# HB-UNI-SenAct-8-8-RC_V1_2.net
KiCad netlist of a schematic drawn in EAGLE
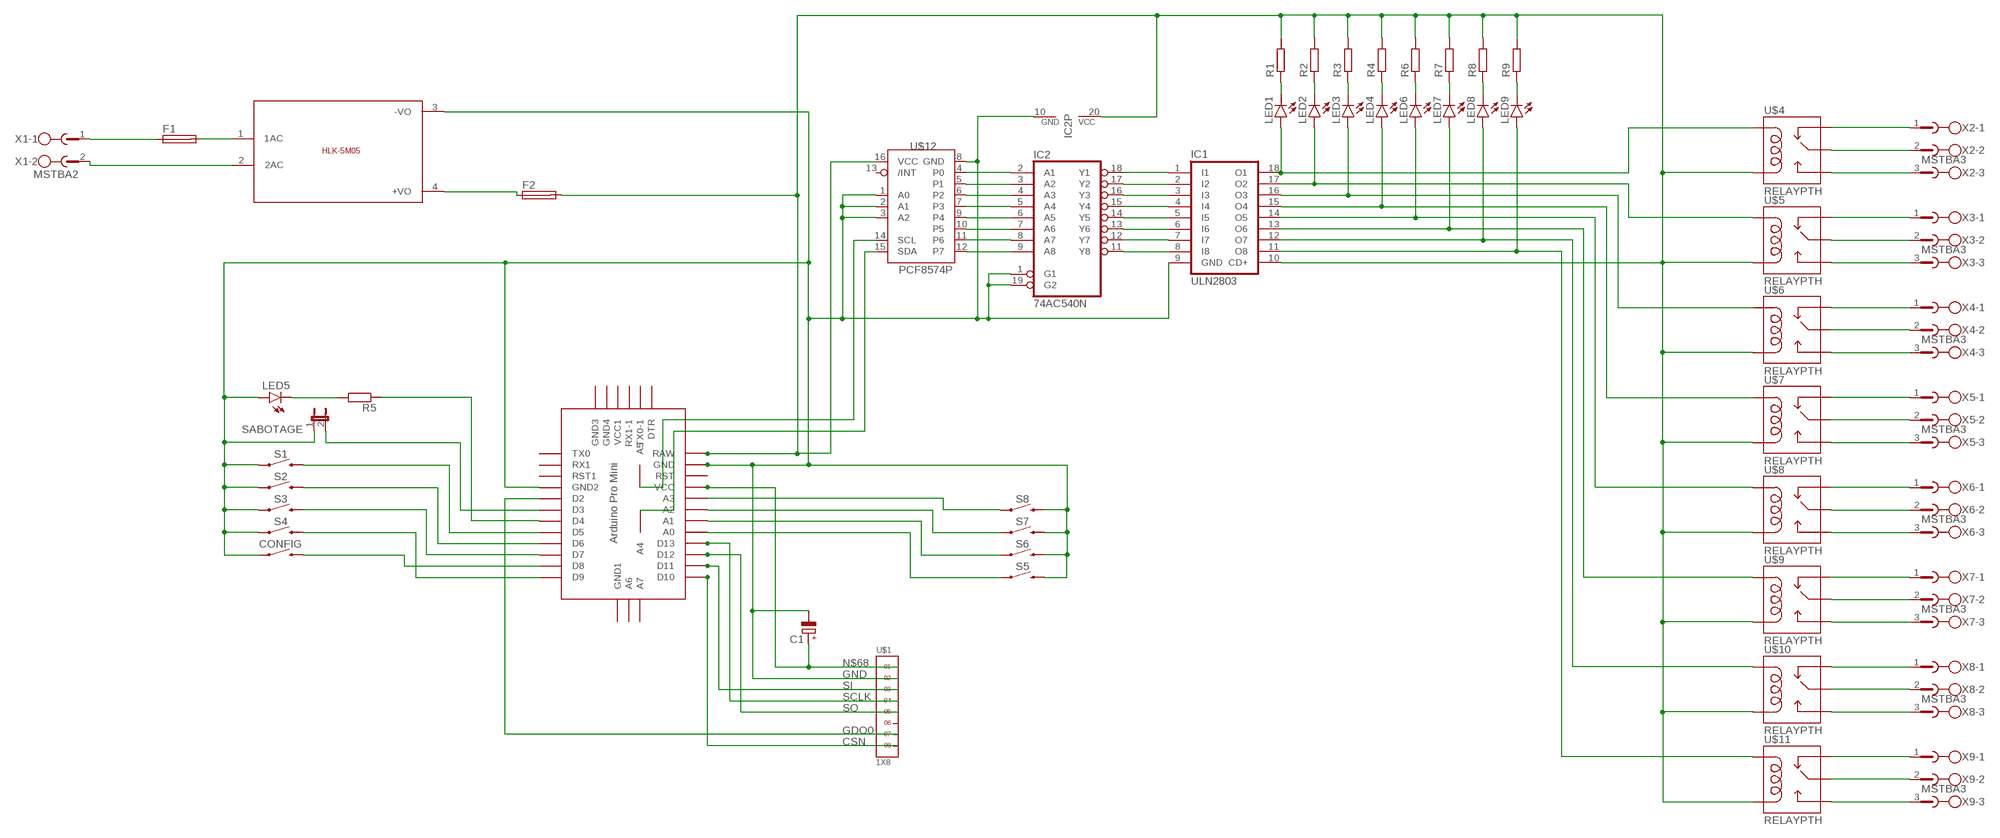
[diagram p0: schematic, sheet 1]

(export (version "E")
  (design (tool "Eeschema 10.0.6"))
  (components
    (comp (ref "C1")
      (value "CPOL-EUE2.5-5")
      (footprint "eagle-import:E2,5-5")
      (libsource (lib "eagle-import") (part "CPOL-EUE2.5-5"))
    )
    (comp (ref "CONFIG")
      (value "MOMENTARY-SWITCH-SPST-PTH-6.0MM-KIT")
      (footprint "eagle-import:TACTILE_SWITCH_PTH_6.0MM_KIT")
      (libsource (lib "eagle-import") (part "MOMENTARY-SWITCH-SPST-PTH-6.0MM-KIT"))
    )
    (comp (ref "F1")
      (value "SH22,5A")
      (footprint "eagle-import:SH22,5A")
      (fields (field (name "MPN") "0031.7701.11"))
      (libsource (lib "eagle-import") (part "SH22,5A"))
    )
    (comp (ref "F2")
      (value "SH22,5A")
      (footprint "eagle-import:SH22,5A")
      (fields (field (name "MPN") "0031.7701.11"))
      (libsource (lib "eagle-import") (part "SH22,5A"))
    )
    (comp (ref "IC1")
      (value "ULN2803")
      (footprint "eagle-import:DIL18")
      (libsource (lib "eagle-import") (part "ULN2803A"))
    )
    (comp (ref "IC2")
      (value "74AC540N")
      (footprint "eagle-import:DIL20")
      (libsource (lib "eagle-import") (part "74540NAC"))
    )
    (comp (ref "LED1")
      (value "LED3MM")
      (footprint "eagle-import:LED3MM")
      (libsource (lib "eagle-import") (part "LED3MM"))
    )
    (comp (ref "LED2")
      (value "LED3MM")
      (footprint "eagle-import:LED3MM")
      (libsource (lib "eagle-import") (part "LED3MM"))
    )
    (comp (ref "LED3")
      (value "LED3MM")
      (footprint "eagle-import:LED3MM")
      (libsource (lib "eagle-import") (part "LED3MM"))
    )
    (comp (ref "LED4")
      (value "LED3MM")
      (footprint "eagle-import:LED3MM")
      (libsource (lib "eagle-import") (part "LED3MM"))
    )
    (comp (ref "LED5")
      (value "LED3MM")
      (footprint "eagle-import:LED3MM")
      (libsource (lib "eagle-import") (part "LED3MM"))
    )
    (comp (ref "LED6")
      (value "LED3MM")
      (footprint "eagle-import:LED3MM")
      (libsource (lib "eagle-import") (part "LED3MM"))
    )
    (comp (ref "LED7")
      (value "LED3MM")
      (footprint "eagle-import:LED3MM")
      (libsource (lib "eagle-import") (part "LED3MM"))
    )
    (comp (ref "LED8")
      (value "LED3MM")
      (footprint "eagle-import:LED3MM")
      (libsource (lib "eagle-import") (part "LED3MM"))
    )
    (comp (ref "LED9")
      (value "LED3MM")
      (footprint "eagle-import:LED3MM")
      (libsource (lib "eagle-import") (part "LED3MM"))
    )
    (comp (ref "R1")
      (value "R-EU_0309/10")
      (footprint "eagle-import:0309_10")
      (libsource (lib "eagle-import") (part "R-EU_0309/10"))
    )
    (comp (ref "R2")
      (value "R-EU_0309/10")
      (footprint "eagle-import:0309_10")
      (libsource (lib "eagle-import") (part "R-EU_0309/10"))
    )
    (comp (ref "R3")
      (value "R-EU_0309/10")
      (footprint "eagle-import:0309_10")
      (libsource (lib "eagle-import") (part "R-EU_0309/10"))
    )
    (comp (ref "R4")
      (value "R-EU_0309/10")
      (footprint "eagle-import:0309_10")
      (libsource (lib "eagle-import") (part "R-EU_0309/10"))
    )
    (comp (ref "R5")
      (value "R-EU_0309/10")
      (footprint "eagle-import:0309_10")
      (libsource (lib "eagle-import") (part "R-EU_0309/10"))
    )
    (comp (ref "R6")
      (value "R-EU_0309/10")
      (footprint "eagle-import:0309_10")
      (libsource (lib "eagle-import") (part "R-EU_0309/10"))
    )
    (comp (ref "R7")
      (value "R-EU_0309/10")
      (footprint "eagle-import:0309_10")
      (libsource (lib "eagle-import") (part "R-EU_0309/10"))
    )
    (comp (ref "R8")
      (value "R-EU_0309/10")
      (footprint "eagle-import:0309_10")
      (libsource (lib "eagle-import") (part "R-EU_0309/10"))
    )
    (comp (ref "R9")
      (value "R-EU_0309/10")
      (footprint "eagle-import:0309_10")
      (libsource (lib "eagle-import") (part "R-EU_0309/10"))
    )
    (comp (ref "S1")
      (value "MOMENTARY-SWITCH-SPST-PTH-6.0MM")
      (footprint "eagle-import:TACTILE_SWITCH_PTH_6.0MM")
      (libsource (lib "eagle-import") (part "MOMENTARY-SWITCH-SPST-PTH-6.0MM"))
    )
    (comp (ref "S2")
      (value "MOMENTARY-SWITCH-SPST-PTH-6.0MM-KIT")
      (footprint "eagle-import:TACTILE_SWITCH_PTH_6.0MM_KIT")
      (libsource (lib "eagle-import") (part "MOMENTARY-SWITCH-SPST-PTH-6.0MM-KIT"))
    )
    (comp (ref "S3")
      (value "MOMENTARY-SWITCH-SPST-PTH-6.0MM-KIT")
      (footprint "eagle-import:TACTILE_SWITCH_PTH_6.0MM_KIT")
      (libsource (lib "eagle-import") (part "MOMENTARY-SWITCH-SPST-PTH-6.0MM-KIT"))
    )
    (comp (ref "S4")
      (value "MOMENTARY-SWITCH-SPST-PTH-6.0MM-KIT")
      (footprint "eagle-import:TACTILE_SWITCH_PTH_6.0MM_KIT")
      (libsource (lib "eagle-import") (part "MOMENTARY-SWITCH-SPST-PTH-6.0MM-KIT"))
    )
    (comp (ref "S5")
      (value "MOMENTARY-SWITCH-SPST-PTH-6.0MM-KIT")
      (footprint "eagle-import:TACTILE_SWITCH_PTH_6.0MM_KIT")
      (libsource (lib "eagle-import") (part "MOMENTARY-SWITCH-SPST-PTH-6.0MM-KIT"))
    )
    (comp (ref "S6")
      (value "MOMENTARY-SWITCH-SPST-PTH-6.0MM-KIT")
      (footprint "eagle-import:TACTILE_SWITCH_PTH_6.0MM_KIT")
      (libsource (lib "eagle-import") (part "MOMENTARY-SWITCH-SPST-PTH-6.0MM-KIT"))
    )
    (comp (ref "S7")
      (value "MOMENTARY-SWITCH-SPST-PTH-6.0MM-KIT")
      (footprint "eagle-import:TACTILE_SWITCH_PTH_6.0MM_KIT")
      (libsource (lib "eagle-import") (part "MOMENTARY-SWITCH-SPST-PTH-6.0MM-KIT"))
    )
    (comp (ref "S8")
      (value "MOMENTARY-SWITCH-SPST-PTH-6.0MM-KIT")
      (footprint "eagle-import:TACTILE_SWITCH_PTH_6.0MM_KIT")
      (libsource (lib "eagle-import") (part "MOMENTARY-SWITCH-SPST-PTH-6.0MM-KIT"))
    )
    (comp (ref "SABOTAGE")
      (value "JP1E")
      (footprint "eagle-import:JP1")
      (libsource (lib "eagle-import") (part "JP1E"))
    )
    (comp (ref "U$1")
      (value "1X8")
      (footprint "eagle-import:1X8")
      (libsource (lib "eagle-import") (part "1X8"))
    )
    (comp (ref "U$2")
      (value "ABK-PRO-MINI")
      (footprint "eagle-import:ABK-PRO-MINI")
      (libsource (lib "eagle-import") (part "ABK-PRO-MINI"))
    )
    (comp (ref "U$3")
      (value "5VDC/5W")
      (footprint "eagle-import:HLK-5M05")
      (libsource (lib "eagle-import") (part "HLK-5M05"))
    )
    (comp (ref "U$4")
      (value "RELAYPTH")
      (footprint "eagle-import:SRD-05VDC-SL-C")
      (libsource (lib "eagle-import") (part "RELAYPTH"))
    )
    (comp (ref "U$5")
      (value "RELAYPTH")
      (footprint "eagle-import:SRD-05VDC-SL-C")
      (libsource (lib "eagle-import") (part "RELAYPTH"))
    )
    (comp (ref "U$6")
      (value "RELAYPTH")
      (footprint "eagle-import:SRD-05VDC-SL-C")
      (libsource (lib "eagle-import") (part "RELAYPTH"))
    )
    (comp (ref "U$7")
      (value "RELAYPTH")
      (footprint "eagle-import:SRD-05VDC-SL-C")
      (libsource (lib "eagle-import") (part "RELAYPTH"))
    )
    (comp (ref "U$8")
      (value "RELAYPTH")
      (footprint "eagle-import:SRD-05VDC-SL-C")
      (libsource (lib "eagle-import") (part "RELAYPTH"))
    )
    (comp (ref "U$9")
      (value "RELAYPTH")
      (footprint "eagle-import:SRD-05VDC-SL-C")
      (libsource (lib "eagle-import") (part "RELAYPTH"))
    )
    (comp (ref "U$10")
      (value "RELAYPTH")
      (footprint "eagle-import:SRD-05VDC-SL-C")
      (libsource (lib "eagle-import") (part "RELAYPTH"))
    )
    (comp (ref "U$11")
      (value "RELAYPTH")
      (footprint "eagle-import:SRD-05VDC-SL-C")
      (libsource (lib "eagle-import") (part "RELAYPTH"))
    )
    (comp (ref "U$12")
      (value "PCF8574P")
      (footprint "eagle-import:DIL16")
      (libsource (lib "eagle-import") (part "PCF8574P"))
    )
    (comp (ref "X1")
      (value "MSTBA2")
      (footprint "eagle-import:MSTBA2")
      (fields (field (name "MF") "FARNELL") (field (name "MPN") "1757242"))
      (libsource (lib "eagle-import") (part "MSTBA2"))
    )
    (comp (ref "X2")
      (value "MSTBA3")
      (footprint "eagle-import:MSTBA3")
      (fields (field (name "MF") "FARNELL") (field (name "MPN") "1757255"))
      (libsource (lib "eagle-import") (part "MSTBA3"))
    )
    (comp (ref "X3")
      (value "MSTBA3")
      (footprint "eagle-import:MSTBA3")
      (fields (field (name "MF") "FARNELL") (field (name "MPN") "1757255"))
      (libsource (lib "eagle-import") (part "MSTBA3"))
    )
    (comp (ref "X4")
      (value "MSTBA3")
      (footprint "eagle-import:MSTBA3")
      (fields (field (name "MF") "FARNELL") (field (name "MPN") "1757255"))
      (libsource (lib "eagle-import") (part "MSTBA3"))
    )
    (comp (ref "X5")
      (value "MSTBA3")
      (footprint "eagle-import:MSTBA3")
      (fields (field (name "MF") "FARNELL") (field (name "MPN") "1757255"))
      (libsource (lib "eagle-import") (part "MSTBA3"))
    )
    (comp (ref "X6")
      (value "MSTBA3")
      (footprint "eagle-import:MSTBA3")
      (fields (field (name "MF") "FARNELL") (field (name "MPN") "1757255"))
      (libsource (lib "eagle-import") (part "MSTBA3"))
    )
    (comp (ref "X7")
      (value "MSTBA3")
      (footprint "eagle-import:MSTBA3")
      (fields (field (name "MF") "FARNELL") (field (name "MPN") "1757255"))
      (libsource (lib "eagle-import") (part "MSTBA3"))
    )
    (comp (ref "X8")
      (value "MSTBA3")
      (footprint "eagle-import:MSTBA3")
      (fields (field (name "MF") "FARNELL") (field (name "MPN") "1757255"))
      (libsource (lib "eagle-import") (part "MSTBA3"))
    )
    (comp (ref "X9")
      (value "MSTBA3")
      (footprint "eagle-import:MSTBA3")
      (fields (field (name "MF") "FARNELL") (field (name "MPN") "1757255"))
      (libsource (lib "eagle-import") (part "MSTBA3"))
    )
  )
  (nets
    (net (code "1") (name "/CSN") (class "Default")
      (node (ref "U$1") (pin "8") (pinfunction "8_8") (pintype "bidirectional"))
      (node (ref "U$2") (pin "D10") (pinfunction "D10_D10") (pintype "bidirectional"))
    )
    (net (code "2") (name "/GDO0") (class "Default")
      (node (ref "U$1") (pin "7") (pinfunction "7_7") (pintype "bidirectional"))
      (node (ref "U$2") (pin "D2") (pinfunction "D2_D2") (pintype "bidirectional"))
    )
    (net (code "3") (name "/GND") (class "Default")
      (node (ref "C1") (pin "-") (pinfunction "-_-") (pintype "passive"))
      (node (ref "CONFIG") (pin "1") (pinfunction "1_1") (pintype "passive"))
      (node (ref "IC1") (pin "9") (pinfunction "GND_9") (pintype "power_in"))
      (node (ref "IC2") (pin "1") (pinfunction "G1_1") (pintype "input"))
      (node (ref "IC2") (pin "10") (pinfunction "GND_10") (pintype "power_in"))
      (node (ref "IC2") (pin "19") (pinfunction "G2_19") (pintype "input"))
      (node (ref "LED5") (pin "A") (pinfunction "A_A") (pintype "passive"))
      (node (ref "S1") (pin "1") (pinfunction "1_1") (pintype "passive"))
      (node (ref "S2") (pin "1") (pinfunction "1_1") (pintype "passive"))
      (node (ref "S3") (pin "1") (pinfunction "1_1") (pintype "passive"))
      (node (ref "S4") (pin "1") (pinfunction "1_1") (pintype "passive"))
      (node (ref "S5") (pin "3") (pinfunction "2_3") (pintype "passive"))
      (node (ref "S6") (pin "3") (pinfunction "2_3") (pintype "passive"))
      (node (ref "S7") (pin "3") (pinfunction "2_3") (pintype "passive"))
      (node (ref "S8") (pin "3") (pinfunction "2_3") (pintype "passive"))
      (node (ref "SABOTAGE") (pin "1") (pinfunction "1_1") (pintype "passive"))
      (node (ref "U$1") (pin "2") (pinfunction "2_2") (pintype "bidirectional"))
      (node (ref "U$12") (pin "1") (pinfunction "A0_1") (pintype "input"))
      (node (ref "U$12") (pin "2") (pinfunction "A1_2") (pintype "input"))
      (node (ref "U$12") (pin "3") (pinfunction "A2_3") (pintype "input"))
      (node (ref "U$12") (pin "8") (pinfunction "GND_8") (pintype "power_in"))
      (node (ref "U$2") (pin "GND") (pinfunction "GND_GND") (pintype "bidirectional"))
      (node (ref "U$2") (pin "GND1") (pinfunction "GND2_GND1") (pintype "bidirectional"))
      (node (ref "U$3") (pin "3") (pinfunction "-VO_3") (pintype "bidirectional"))
    )
    (net (code "4") (name "/N$68") (class "Default")
      (node (ref "C1") (pin "+") (pinfunction "+_+") (pintype "passive"))
      (node (ref "U$1") (pin "1") (pinfunction "1_1") (pintype "bidirectional"))
      (node (ref "U$2") (pin "VCC") (pinfunction "VCC_VCC") (pintype "bidirectional"))
    )
    (net (code "5") (name "/SCLK") (class "Default")
      (node (ref "U$1") (pin "4") (pinfunction "4_4") (pintype "bidirectional"))
      (node (ref "U$2") (pin "D13") (pinfunction "D13_D13") (pintype "bidirectional"))
    )
    (net (code "6") (name "/SI") (class "Default")
      (node (ref "U$1") (pin "3") (pinfunction "3_3") (pintype "bidirectional"))
      (node (ref "U$2") (pin "D11") (pinfunction "D11_D11") (pintype "bidirectional"))
    )
    (net (code "7") (name "/SO") (class "Default")
      (node (ref "U$1") (pin "5") (pinfunction "5_5") (pintype "bidirectional"))
      (node (ref "U$2") (pin "D12") (pinfunction "D12_D12") (pintype "bidirectional"))
    )
    (net (code "8") (name "Net-(CONFIG-2)") (class "Default")
      (node (ref "CONFIG") (pin "3") (pinfunction "2_3") (pintype "passive"))
      (node (ref "U$2") (pin "D8") (pinfunction "D8_D8") (pintype "bidirectional"))
    )
    (net (code "9") (name "Net-(F1-Pad1)") (class "Default")
      (node (ref "F1") (pin "1") (pinfunction "1_1") (pintype "passive"))
      (node (ref "X1") (pin "1") (pinfunction "1_1") (pintype "passive"))
    )
    (net (code "10") (name "Net-(IC1-CD+)") (class "Default")
      (node (ref "F2") (pin "2") (pinfunction "2_2") (pintype "passive"))
      (node (ref "IC1") (pin "10") (pinfunction "CD+_10") (pintype "passive"))
      (node (ref "IC2") (pin "20") (pinfunction "VCC_20") (pintype "power_in"))
      (node (ref "R1") (pin "2") (pinfunction "2_2") (pintype "passive"))
      (node (ref "R2") (pin "2") (pinfunction "2_2") (pintype "passive"))
      (node (ref "R3") (pin "2") (pinfunction "2_2") (pintype "passive"))
      (node (ref "R4") (pin "2") (pinfunction "2_2") (pintype "passive"))
      (node (ref "R6") (pin "2") (pinfunction "2_2") (pintype "passive"))
      (node (ref "R7") (pin "2") (pinfunction "2_2") (pintype "passive"))
      (node (ref "R8") (pin "2") (pinfunction "2_2") (pintype "passive"))
      (node (ref "R9") (pin "2") (pinfunction "2_2") (pintype "passive"))
      (node (ref "U$10") (pin "COIL0") (pinfunction "COIL0_COIL0") (pintype "bidirectional"))
      (node (ref "U$11") (pin "COIL0") (pinfunction "COIL0_COIL0") (pintype "bidirectional"))
      (node (ref "U$12") (pin "16") (pinfunction "VCC_16") (pintype "power_in"))
      (node (ref "U$2") (pin "RAW") (pinfunction "RAW_RAW") (pintype "bidirectional"))
      (node (ref "U$4") (pin "COIL0") (pinfunction "COIL0_COIL0") (pintype "bidirectional"))
      (node (ref "U$5") (pin "COIL0") (pinfunction "COIL0_COIL0") (pintype "bidirectional"))
      (node (ref "U$6") (pin "COIL0") (pinfunction "COIL0_COIL0") (pintype "bidirectional"))
      (node (ref "U$7") (pin "COIL0") (pinfunction "COIL0_COIL0") (pintype "bidirectional"))
      (node (ref "U$8") (pin "COIL0") (pinfunction "COIL0_COIL0") (pintype "bidirectional"))
      (node (ref "U$9") (pin "COIL0") (pinfunction "COIL0_COIL0") (pintype "bidirectional"))
    )
    (net (code "11") (name "Net-(IC1-I1)") (class "Default")
      (node (ref "IC1") (pin "1") (pinfunction "I1_1") (pintype "input"))
      (node (ref "IC2") (pin "18") (pinfunction "Y1_18") (pintype "tri_state"))
    )
    (net (code "12") (name "Net-(IC1-I2)") (class "Default")
      (node (ref "IC1") (pin "2") (pinfunction "I2_2") (pintype "input"))
      (node (ref "IC2") (pin "17") (pinfunction "Y2_17") (pintype "tri_state"))
    )
    (net (code "13") (name "Net-(IC1-I3)") (class "Default")
      (node (ref "IC1") (pin "3") (pinfunction "I3_3") (pintype "input"))
      (node (ref "IC2") (pin "16") (pinfunction "Y3_16") (pintype "tri_state"))
    )
    (net (code "14") (name "Net-(IC1-I4)") (class "Default")
      (node (ref "IC1") (pin "4") (pinfunction "I4_4") (pintype "input"))
      (node (ref "IC2") (pin "15") (pinfunction "Y4_15") (pintype "tri_state"))
    )
    (net (code "15") (name "Net-(IC1-I5)") (class "Default")
      (node (ref "IC1") (pin "5") (pinfunction "I5_5") (pintype "input"))
      (node (ref "IC2") (pin "14") (pinfunction "Y5_14") (pintype "tri_state"))
    )
    (net (code "16") (name "Net-(IC1-I6)") (class "Default")
      (node (ref "IC1") (pin "6") (pinfunction "I6_6") (pintype "input"))
      (node (ref "IC2") (pin "13") (pinfunction "Y6_13") (pintype "tri_state"))
    )
    (net (code "17") (name "Net-(IC1-I7)") (class "Default")
      (node (ref "IC1") (pin "7") (pinfunction "I7_7") (pintype "input"))
      (node (ref "IC2") (pin "12") (pinfunction "Y7_12") (pintype "tri_state"))
    )
    (net (code "18") (name "Net-(IC1-I8)") (class "Default")
      (node (ref "IC1") (pin "8") (pinfunction "I8_8") (pintype "input"))
      (node (ref "IC2") (pin "11") (pinfunction "Y8_11") (pintype "tri_state"))
    )
    (net (code "19") (name "Net-(IC1-O1)") (class "Default")
      (node (ref "IC1") (pin "18") (pinfunction "O1_18") (pintype "open_collector"))
      (node (ref "LED1") (pin "A") (pinfunction "A_A") (pintype "passive"))
      (node (ref "U$4") (pin "COIL1") (pinfunction "COIL1_COIL1") (pintype "bidirectional"))
    )
    (net (code "20") (name "Net-(IC1-O2)") (class "Default")
      (node (ref "IC1") (pin "17") (pinfunction "O2_17") (pintype "open_collector"))
      (node (ref "LED2") (pin "A") (pinfunction "A_A") (pintype "passive"))
      (node (ref "U$5") (pin "COIL1") (pinfunction "COIL1_COIL1") (pintype "bidirectional"))
    )
    (net (code "21") (name "Net-(IC1-O3)") (class "Default")
      (node (ref "IC1") (pin "16") (pinfunction "O3_16") (pintype "open_collector"))
      (node (ref "LED3") (pin "A") (pinfunction "A_A") (pintype "passive"))
      (node (ref "U$6") (pin "COIL1") (pinfunction "COIL1_COIL1") (pintype "bidirectional"))
    )
    (net (code "22") (name "Net-(IC1-O4)") (class "Default")
      (node (ref "IC1") (pin "15") (pinfunction "O4_15") (pintype "open_collector"))
      (node (ref "LED4") (pin "A") (pinfunction "A_A") (pintype "passive"))
      (node (ref "U$7") (pin "COIL1") (pinfunction "COIL1_COIL1") (pintype "bidirectional"))
    )
    (net (code "23") (name "Net-(IC1-O5)") (class "Default")
      (node (ref "IC1") (pin "14") (pinfunction "O5_14") (pintype "open_collector"))
      (node (ref "LED6") (pin "A") (pinfunction "A_A") (pintype "passive"))
      (node (ref "U$8") (pin "COIL1") (pinfunction "COIL1_COIL1") (pintype "bidirectional"))
    )
    (net (code "24") (name "Net-(IC1-O6)") (class "Default")
      (node (ref "IC1") (pin "13") (pinfunction "O6_13") (pintype "open_collector"))
      (node (ref "LED7") (pin "A") (pinfunction "A_A") (pintype "passive"))
      (node (ref "U$9") (pin "COIL1") (pinfunction "COIL1_COIL1") (pintype "bidirectional"))
    )
    (net (code "25") (name "Net-(IC1-O7)") (class "Default")
      (node (ref "IC1") (pin "12") (pinfunction "O7_12") (pintype "open_collector"))
      (node (ref "LED8") (pin "A") (pinfunction "A_A") (pintype "passive"))
      (node (ref "U$10") (pin "COIL1") (pinfunction "COIL1_COIL1") (pintype "bidirectional"))
    )
    (net (code "26") (name "Net-(IC1-O8)") (class "Default")
      (node (ref "IC1") (pin "11") (pinfunction "O8_11") (pintype "open_collector"))
      (node (ref "LED9") (pin "A") (pinfunction "A_A") (pintype "passive"))
      (node (ref "U$11") (pin "COIL1") (pinfunction "COIL1_COIL1") (pintype "bidirectional"))
    )
    (net (code "27") (name "Net-(IC2A-A1)") (class "Default")
      (node (ref "IC2") (pin "2") (pinfunction "A1_2") (pintype "input"))
      (node (ref "U$12") (pin "4") (pinfunction "P0_4") (pintype "bidirectional"))
    )
    (net (code "28") (name "Net-(IC2A-A2)") (class "Default")
      (node (ref "IC2") (pin "3") (pinfunction "A2_3") (pintype "input"))
      (node (ref "U$12") (pin "5") (pinfunction "P1_5") (pintype "bidirectional"))
    )
    (net (code "29") (name "Net-(IC2A-A3)") (class "Default")
      (node (ref "IC2") (pin "4") (pinfunction "A3_4") (pintype "input"))
      (node (ref "U$12") (pin "6") (pinfunction "P2_6") (pintype "bidirectional"))
    )
    (net (code "30") (name "Net-(IC2A-A4)") (class "Default")
      (node (ref "IC2") (pin "5") (pinfunction "A4_5") (pintype "input"))
      (node (ref "U$12") (pin "7") (pinfunction "P3_7") (pintype "bidirectional"))
    )
    (net (code "31") (name "Net-(IC2A-A5)") (class "Default")
      (node (ref "IC2") (pin "6") (pinfunction "A5_6") (pintype "input"))
      (node (ref "U$12") (pin "9") (pinfunction "P4_9") (pintype "bidirectional"))
    )
    (net (code "32") (name "Net-(IC2A-A6)") (class "Default")
      (node (ref "IC2") (pin "7") (pinfunction "A6_7") (pintype "input"))
      (node (ref "U$12") (pin "10") (pinfunction "P5_10") (pintype "bidirectional"))
    )
    (net (code "33") (name "Net-(IC2A-A7)") (class "Default")
      (node (ref "IC2") (pin "8") (pinfunction "A7_8") (pintype "input"))
      (node (ref "U$12") (pin "11") (pinfunction "P6_11") (pintype "bidirectional"))
    )
    (net (code "34") (name "Net-(IC2A-A8)") (class "Default")
      (node (ref "IC2") (pin "9") (pinfunction "A8_9") (pintype "input"))
      (node (ref "U$12") (pin "12") (pinfunction "P7_12") (pintype "bidirectional"))
    )
    (net (code "35") (name "Net-(LED1-C)") (class "Default")
      (node (ref "LED1") (pin "K") (pinfunction "C_K") (pintype "passive"))
      (node (ref "R1") (pin "1") (pinfunction "1_1") (pintype "passive"))
    )
    (net (code "36") (name "Net-(LED2-C)") (class "Default")
      (node (ref "LED2") (pin "K") (pinfunction "C_K") (pintype "passive"))
      (node (ref "R2") (pin "1") (pinfunction "1_1") (pintype "passive"))
    )
    (net (code "37") (name "Net-(LED3-C)") (class "Default")
      (node (ref "LED3") (pin "K") (pinfunction "C_K") (pintype "passive"))
      (node (ref "R3") (pin "1") (pinfunction "1_1") (pintype "passive"))
    )
    (net (code "38") (name "Net-(LED4-C)") (class "Default")
      (node (ref "LED4") (pin "K") (pinfunction "C_K") (pintype "passive"))
      (node (ref "R4") (pin "1") (pinfunction "1_1") (pintype "passive"))
    )
    (net (code "39") (name "Net-(LED5-C)") (class "Default")
      (node (ref "LED5") (pin "K") (pinfunction "C_K") (pintype "passive"))
      (node (ref "R5") (pin "2") (pinfunction "2_2") (pintype "passive"))
    )
    (net (code "40") (name "Net-(LED6-C)") (class "Default")
      (node (ref "LED6") (pin "K") (pinfunction "C_K") (pintype "passive"))
      (node (ref "R6") (pin "1") (pinfunction "1_1") (pintype "passive"))
    )
    (net (code "41") (name "Net-(LED7-C)") (class "Default")
      (node (ref "LED7") (pin "K") (pinfunction "C_K") (pintype "passive"))
      (node (ref "R7") (pin "1") (pinfunction "1_1") (pintype "passive"))
    )
    (net (code "42") (name "Net-(LED8-C)") (class "Default")
      (node (ref "LED8") (pin "K") (pinfunction "C_K") (pintype "passive"))
      (node (ref "R8") (pin "1") (pinfunction "1_1") (pintype "passive"))
    )
    (net (code "43") (name "Net-(LED9-C)") (class "Default")
      (node (ref "LED9") (pin "K") (pinfunction "C_K") (pintype "passive"))
      (node (ref "R9") (pin "1") (pinfunction "1_1") (pintype "passive"))
    )
    (net (code "44") (name "Net-(R5-Pad1)") (class "Default")
      (node (ref "R5") (pin "1") (pinfunction "1_1") (pintype "passive"))
      (node (ref "U$2") (pin "D4") (pinfunction "D4_D4") (pintype "bidirectional"))
    )
    (net (code "45") (name "Net-(S1-2)") (class "Default")
      (node (ref "S1") (pin "3") (pinfunction "2_3") (pintype "passive"))
      (node (ref "U$2") (pin "D5") (pinfunction "D5_D5") (pintype "bidirectional"))
    )
    (net (code "46") (name "Net-(S2-2)") (class "Default")
      (node (ref "S2") (pin "3") (pinfunction "2_3") (pintype "passive"))
      (node (ref "U$2") (pin "D6") (pinfunction "D6_D6") (pintype "bidirectional"))
    )
    (net (code "47") (name "Net-(S3-2)") (class "Default")
      (node (ref "S3") (pin "3") (pinfunction "2_3") (pintype "passive"))
      (node (ref "U$2") (pin "D7") (pinfunction "D7_D7") (pintype "bidirectional"))
    )
    (net (code "48") (name "Net-(S4-2)") (class "Default")
      (node (ref "S4") (pin "3") (pinfunction "2_3") (pintype "passive"))
      (node (ref "U$2") (pin "D9") (pinfunction "D9_D9") (pintype "bidirectional"))
    )
    (net (code "49") (name "Net-(S5-Pad1)") (class "Default")
      (node (ref "S5") (pin "1") (pinfunction "1_1") (pintype "passive"))
      (node (ref "U$2") (pin "A0") (pinfunction "A0_A0") (pintype "bidirectional"))
    )
    (net (code "50") (name "Net-(S6-Pad1)") (class "Default")
      (node (ref "S6") (pin "1") (pinfunction "1_1") (pintype "passive"))
      (node (ref "U$2") (pin "A1") (pinfunction "A1_A1") (pintype "bidirectional"))
    )
    (net (code "51") (name "Net-(S7-Pad1)") (class "Default")
      (node (ref "S7") (pin "1") (pinfunction "1_1") (pintype "passive"))
      (node (ref "U$2") (pin "A2") (pinfunction "A2_A2") (pintype "bidirectional"))
    )
    (net (code "52") (name "Net-(S8-Pad1)") (class "Default")
      (node (ref "S8") (pin "1") (pinfunction "1_1") (pintype "passive"))
      (node (ref "U$2") (pin "A3") (pinfunction "A3_A3") (pintype "bidirectional"))
    )
    (net (code "53") (name "Net-(SABOTAGE-Pad2)") (class "Default")
      (node (ref "SABOTAGE") (pin "2") (pinfunction "2_2") (pintype "passive"))
      (node (ref "U$2") (pin "D3") (pinfunction "D3_D3") (pintype "bidirectional"))
    )
    (net (code "54") (name "Net-(U$3-+VO)") (class "Default")
      (node (ref "F2") (pin "1") (pinfunction "1_1") (pintype "passive"))
      (node (ref "U$3") (pin "4") (pinfunction "+VO_4") (pintype "bidirectional"))
    )
    (net (code "55") (name "Net-(U$3-1AC)") (class "Default")
      (node (ref "F1") (pin "2") (pinfunction "2_2") (pintype "passive"))
      (node (ref "U$3") (pin "1") (pinfunction "1AC_1") (pintype "bidirectional"))
    )
    (net (code "56") (name "Net-(U$3-2AC)") (class "Default")
      (node (ref "U$3") (pin "2") (pinfunction "2AC_2") (pintype "bidirectional"))
      (node (ref "X1") (pin "2") (pinfunction "1_2") (pintype "passive"))
    )
    (net (code "57") (name "Net-(U$4-SWCLOSE)") (class "Default")
      (node (ref "U$4") (pin "SWCLOSED") (pinfunction "SWCLOSE_SWCLOSED") (pintype "bidirectional"))
      (node (ref "X2") (pin "1") (pinfunction "1_1") (pintype "passive"))
    )
    (net (code "58") (name "Net-(U$5-SWCLOSE)") (class "Default")
      (node (ref "U$5") (pin "SWCLOSED") (pinfunction "SWCLOSE_SWCLOSED") (pintype "bidirectional"))
      (node (ref "X3") (pin "1") (pinfunction "1_1") (pintype "passive"))
    )
    (net (code "59") (name "Net-(U$6-SWCLOSE)") (class "Default")
      (node (ref "U$6") (pin "SWCLOSED") (pinfunction "SWCLOSE_SWCLOSED") (pintype "bidirectional"))
      (node (ref "X4") (pin "1") (pinfunction "1_1") (pintype "passive"))
    )
    (net (code "60") (name "Net-(U$7-SWCLOSE)") (class "Default")
      (node (ref "U$7") (pin "SWCLOSED") (pinfunction "SWCLOSE_SWCLOSED") (pintype "bidirectional"))
      (node (ref "X5") (pin "1") (pinfunction "1_1") (pintype "passive"))
    )
    (net (code "61") (name "Net-(U$8-SWCLOSE)") (class "Default")
      (node (ref "U$8") (pin "SWCLOSED") (pinfunction "SWCLOSE_SWCLOSED") (pintype "bidirectional"))
      (node (ref "X6") (pin "1") (pinfunction "1_1") (pintype "passive"))
    )
    (net (code "62") (name "Net-(U$9-SWCLOSE)") (class "Default")
      (node (ref "U$9") (pin "SWCLOSED") (pinfunction "SWCLOSE_SWCLOSED") (pintype "bidirectional"))
      (node (ref "X7") (pin "1") (pinfunction "1_1") (pintype "passive"))
    )
    (net (code "63") (name "Net-(U$10-SWCLOSE)") (class "Default")
      (node (ref "U$10") (pin "SWCLOSED") (pinfunction "SWCLOSE_SWCLOSED") (pintype "bidirectional"))
      (node (ref "X8") (pin "1") (pinfunction "1_1") (pintype "passive"))
    )
    (net (code "64") (name "Net-(U$11-SWCLOSE)") (class "Default")
      (node (ref "U$11") (pin "SWCLOSED") (pinfunction "SWCLOSE_SWCLOSED") (pintype "bidirectional"))
      (node (ref "X9") (pin "1") (pinfunction "1_1") (pintype "passive"))
    )
    (net (code "65") (name "Net-(U$12-SCL)") (class "Default")
      (node (ref "U$12") (pin "14") (pinfunction "SCL_14") (pintype "input"))
      (node (ref "U$2") (pin "A5") (pinfunction "A5_A5") (pintype "bidirectional"))
    )
    (net (code "66") (name "Net-(U$12-SDA)") (class "Default")
      (node (ref "U$12") (pin "15") (pinfunction "SDA_15") (pintype "bidirectional"))
      (node (ref "U$2") (pin "A4") (pinfunction "A4_A4") (pintype "bidirectional"))
    )
    (net (code "67") (name "Net-(X2B-1)") (class "Default")
      (node (ref "U$4") (pin "SWCOMMON") (pinfunction "SWCOMMON_SWCOMMON") (pintype "bidirectional"))
      (node (ref "X2") (pin "2") (pinfunction "1_2") (pintype "passive"))
    )
    (net (code "68") (name "Net-(X2C-1)") (class "Default")
      (node (ref "U$4") (pin "SWOPEN") (pinfunction "SWOPEN_SWOPEN") (pintype "bidirectional"))
      (node (ref "X2") (pin "3") (pinfunction "1_3") (pintype "passive"))
    )
    (net (code "69") (name "Net-(X3B-1)") (class "Default")
      (node (ref "U$5") (pin "SWCOMMON") (pinfunction "SWCOMMON_SWCOMMON") (pintype "bidirectional"))
      (node (ref "X3") (pin "2") (pinfunction "1_2") (pintype "passive"))
    )
    (net (code "70") (name "Net-(X3C-1)") (class "Default")
      (node (ref "U$5") (pin "SWOPEN") (pinfunction "SWOPEN_SWOPEN") (pintype "bidirectional"))
      (node (ref "X3") (pin "3") (pinfunction "1_3") (pintype "passive"))
    )
    (net (code "71") (name "Net-(X4B-1)") (class "Default")
      (node (ref "U$6") (pin "SWCOMMON") (pinfunction "SWCOMMON_SWCOMMON") (pintype "bidirectional"))
      (node (ref "X4") (pin "2") (pinfunction "1_2") (pintype "passive"))
    )
    (net (code "72") (name "Net-(X4C-1)") (class "Default")
      (node (ref "U$6") (pin "SWOPEN") (pinfunction "SWOPEN_SWOPEN") (pintype "bidirectional"))
      (node (ref "X4") (pin "3") (pinfunction "1_3") (pintype "passive"))
    )
    (net (code "73") (name "Net-(X5B-1)") (class "Default")
      (node (ref "U$7") (pin "SWCOMMON") (pinfunction "SWCOMMON_SWCOMMON") (pintype "bidirectional"))
      (node (ref "X5") (pin "2") (pinfunction "1_2") (pintype "passive"))
    )
    (net (code "74") (name "Net-(X5C-1)") (class "Default")
      (node (ref "U$7") (pin "SWOPEN") (pinfunction "SWOPEN_SWOPEN") (pintype "bidirectional"))
      (node (ref "X5") (pin "3") (pinfunction "1_3") (pintype "passive"))
    )
    (net (code "75") (name "Net-(X6B-1)") (class "Default")
      (node (ref "U$8") (pin "SWCOMMON") (pinfunction "SWCOMMON_SWCOMMON") (pintype "bidirectional"))
      (node (ref "X6") (pin "2") (pinfunction "1_2") (pintype "passive"))
    )
    (net (code "76") (name "Net-(X6C-1)") (class "Default")
      (node (ref "U$8") (pin "SWOPEN") (pinfunction "SWOPEN_SWOPEN") (pintype "bidirectional"))
      (node (ref "X6") (pin "3") (pinfunction "1_3") (pintype "passive"))
    )
    (net (code "77") (name "Net-(X7B-1)") (class "Default")
      (node (ref "U$9") (pin "SWCOMMON") (pinfunction "SWCOMMON_SWCOMMON") (pintype "bidirectional"))
      (node (ref "X7") (pin "2") (pinfunction "1_2") (pintype "passive"))
    )
    (net (code "78") (name "Net-(X7C-1)") (class "Default")
      (node (ref "U$9") (pin "SWOPEN") (pinfunction "SWOPEN_SWOPEN") (pintype "bidirectional"))
      (node (ref "X7") (pin "3") (pinfunction "1_3") (pintype "passive"))
    )
    (net (code "79") (name "Net-(X8B-1)") (class "Default")
      (node (ref "U$10") (pin "SWCOMMON") (pinfunction "SWCOMMON_SWCOMMON") (pintype "bidirectional"))
      (node (ref "X8") (pin "2") (pinfunction "1_2") (pintype "passive"))
    )
    (net (code "80") (name "Net-(X8C-1)") (class "Default")
      (node (ref "U$10") (pin "SWOPEN") (pinfunction "SWOPEN_SWOPEN") (pintype "bidirectional"))
      (node (ref "X8") (pin "3") (pinfunction "1_3") (pintype "passive"))
    )
    (net (code "81") (name "Net-(X9B-1)") (class "Default")
      (node (ref "U$11") (pin "SWCOMMON") (pinfunction "SWCOMMON_SWCOMMON") (pintype "bidirectional"))
      (node (ref "X9") (pin "2") (pinfunction "1_2") (pintype "passive"))
    )
    (net (code "82") (name "Net-(X9C-1)") (class "Default")
      (node (ref "U$11") (pin "SWOPEN") (pinfunction "SWOPEN_SWOPEN") (pintype "bidirectional"))
      (node (ref "X9") (pin "3") (pinfunction "1_3") (pintype "passive"))
    )
    (net (code "83") (name "unconnected-(U$1-Pad6)") (class "Default")
      (node (ref "U$1") (pin "6") (pinfunction "6_6") (pintype "bidirectional"))
    )
    (net (code "84") (name "unconnected-(U$2-GND1-PadGND4)") (class "Default")
      (node (ref "U$2") (pin "GND4") (pinfunction "GND1_GND4") (pintype "bidirectional"))
    )
    (net (code "85") (name "unconnected-(U$2-GND3-PadGND2)") (class "Default")
      (node (ref "U$2") (pin "GND2") (pinfunction "GND3_GND2") (pintype "bidirectional"))
    )
    (net (code "86") (name "unconnected-(U$2-GND4-PadGND3)") (class "Default")
      (node (ref "U$2") (pin "GND3") (pinfunction "GND4_GND3") (pintype "bidirectional"))
    )
    (net (code "87") (name "unconnected-(U$2-PadA6)") (class "Default")
      (node (ref "U$2") (pin "A6") (pinfunction "A6_A6") (pintype "bidirectional"))
    )
    (net (code "88") (name "unconnected-(U$2-PadA7)") (class "Default")
      (node (ref "U$2") (pin "A7") (pinfunction "A7_A7") (pintype "bidirectional"))
    )
    (net (code "89") (name "unconnected-(U$2-PadDTR)") (class "Default")
      (node (ref "U$2") (pin "DTR") (pinfunction "DTR_DTR") (pintype "bidirectional"))
    )
    (net (code "90") (name "unconnected-(U$2-PadRST)") (class "Default")
      (node (ref "U$2") (pin "RST") (pinfunction "RST_RST") (pintype "bidirectional"))
    )
    (net (code "91") (name "unconnected-(U$2-PadRST1)") (class "Default")
      (node (ref "U$2") (pin "RST1") (pinfunction "RST1_RST1") (pintype "bidirectional"))
    )
    (net (code "92") (name "unconnected-(U$2-PadRX1)") (class "Default")
      (node (ref "U$2") (pin "RX1") (pinfunction "RX1_RX1") (pintype "bidirectional"))
    )
    (net (code "93") (name "unconnected-(U$2-PadRX1-1)") (class "Default")
      (node (ref "U$2") (pin "RX1-1") (pinfunction "RX1-1_RX1-1") (pintype "bidirectional"))
    )
    (net (code "94") (name "unconnected-(U$2-PadTX0)") (class "Default")
      (node (ref "U$2") (pin "TX0") (pinfunction "TX0_TX0") (pintype "bidirectional"))
    )
    (net (code "95") (name "unconnected-(U$2-PadTX0-1)") (class "Default")
      (node (ref "U$2") (pin "TX0-1") (pinfunction "TX0-1_TX0-1") (pintype "bidirectional"))
    )
    (net (code "96") (name "unconnected-(U$2-PadVCC1)") (class "Default")
      (node (ref "U$2") (pin "VCC1") (pinfunction "VCC1_VCC1") (pintype "bidirectional"))
    )
    (net (code "97") (name "unconnected-(U$12-{slash}INT-Pad13)") (class "Default")
      (node (ref "U$12") (pin "13") (pinfunction "/INT_13") (pintype "output"))
    )
  )
)
